# Isolated-ARD.net
KiCad netlist of a schematic drawn in EAGLE
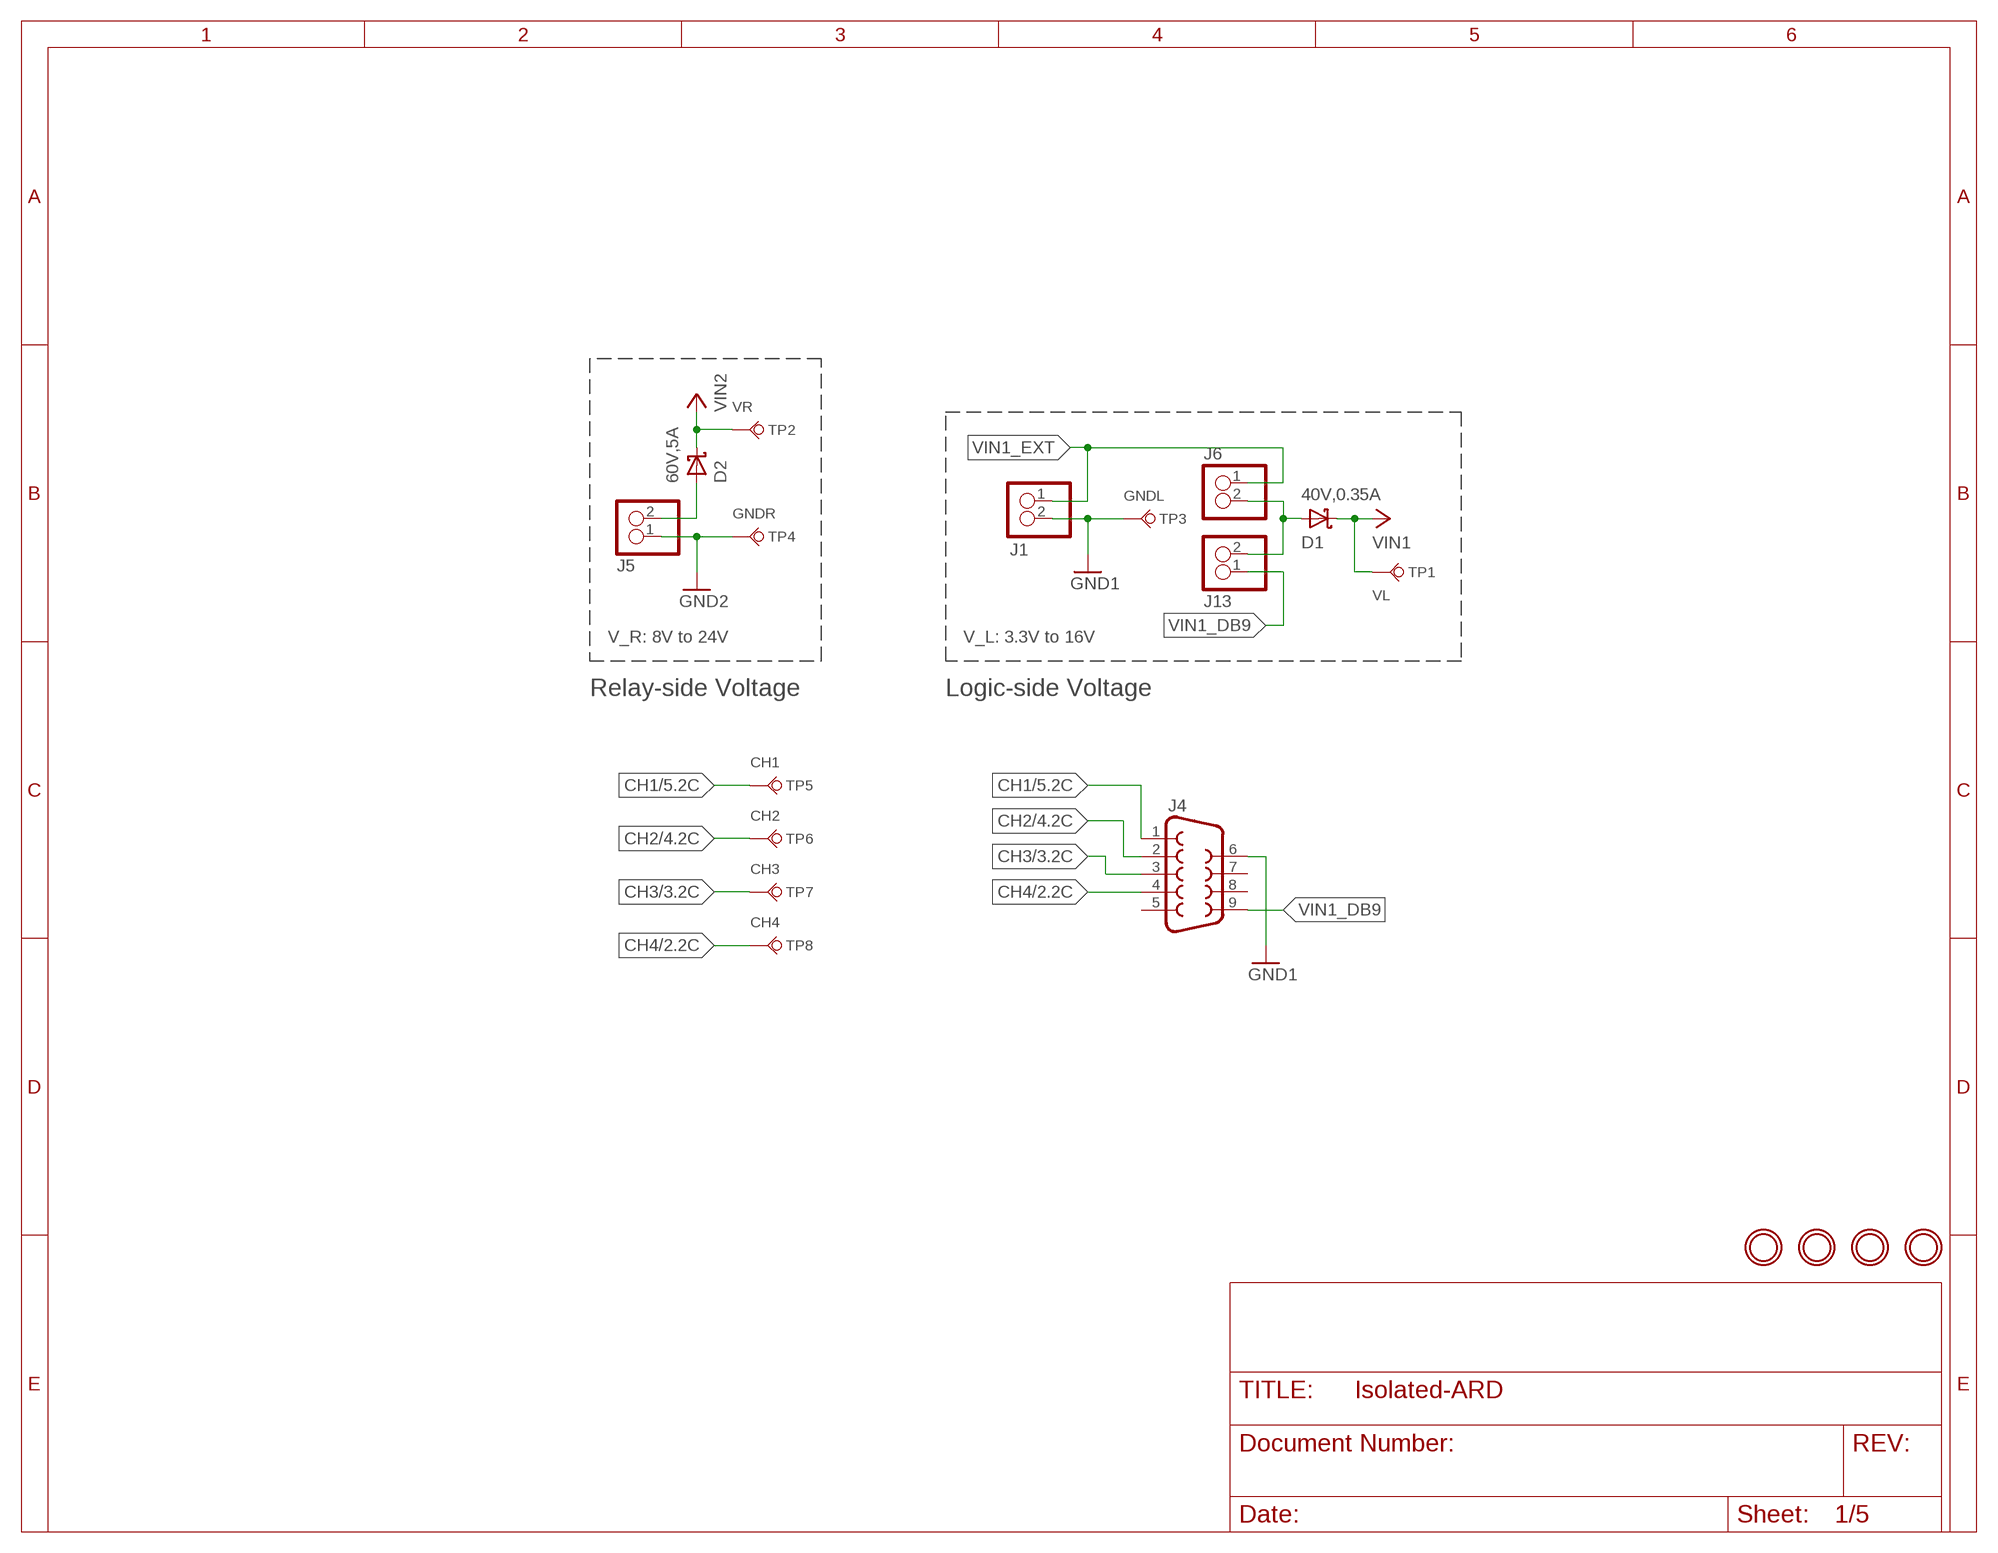
[diagram p0: schematic, sheet 1]
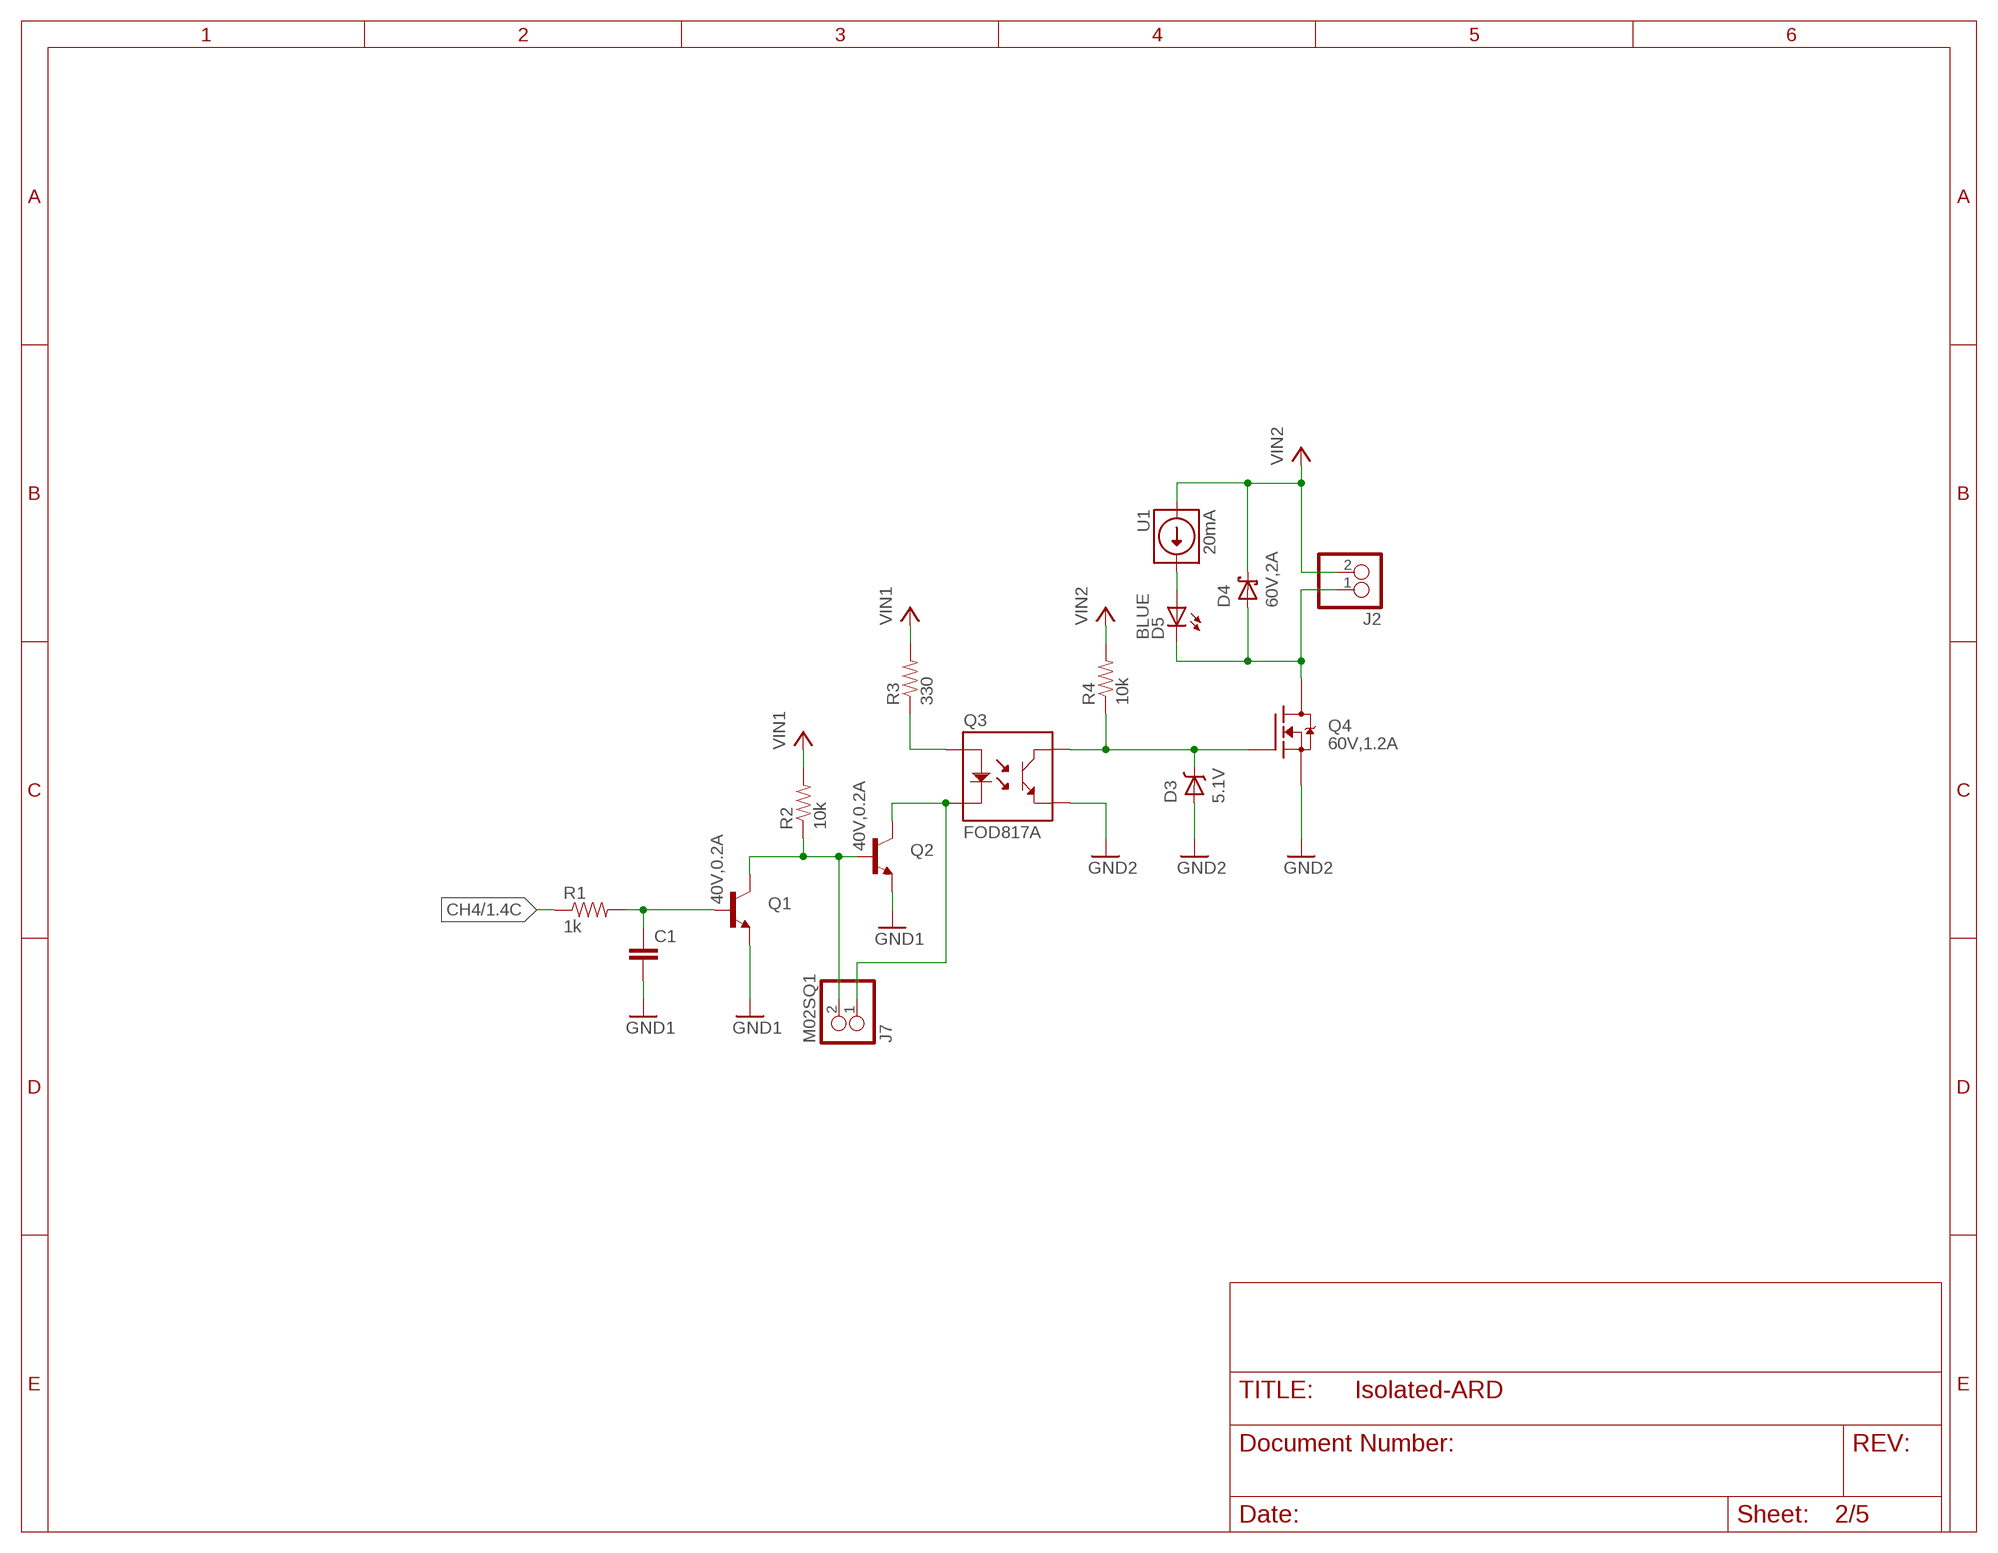
[diagram p1: schematic, sheet 2]
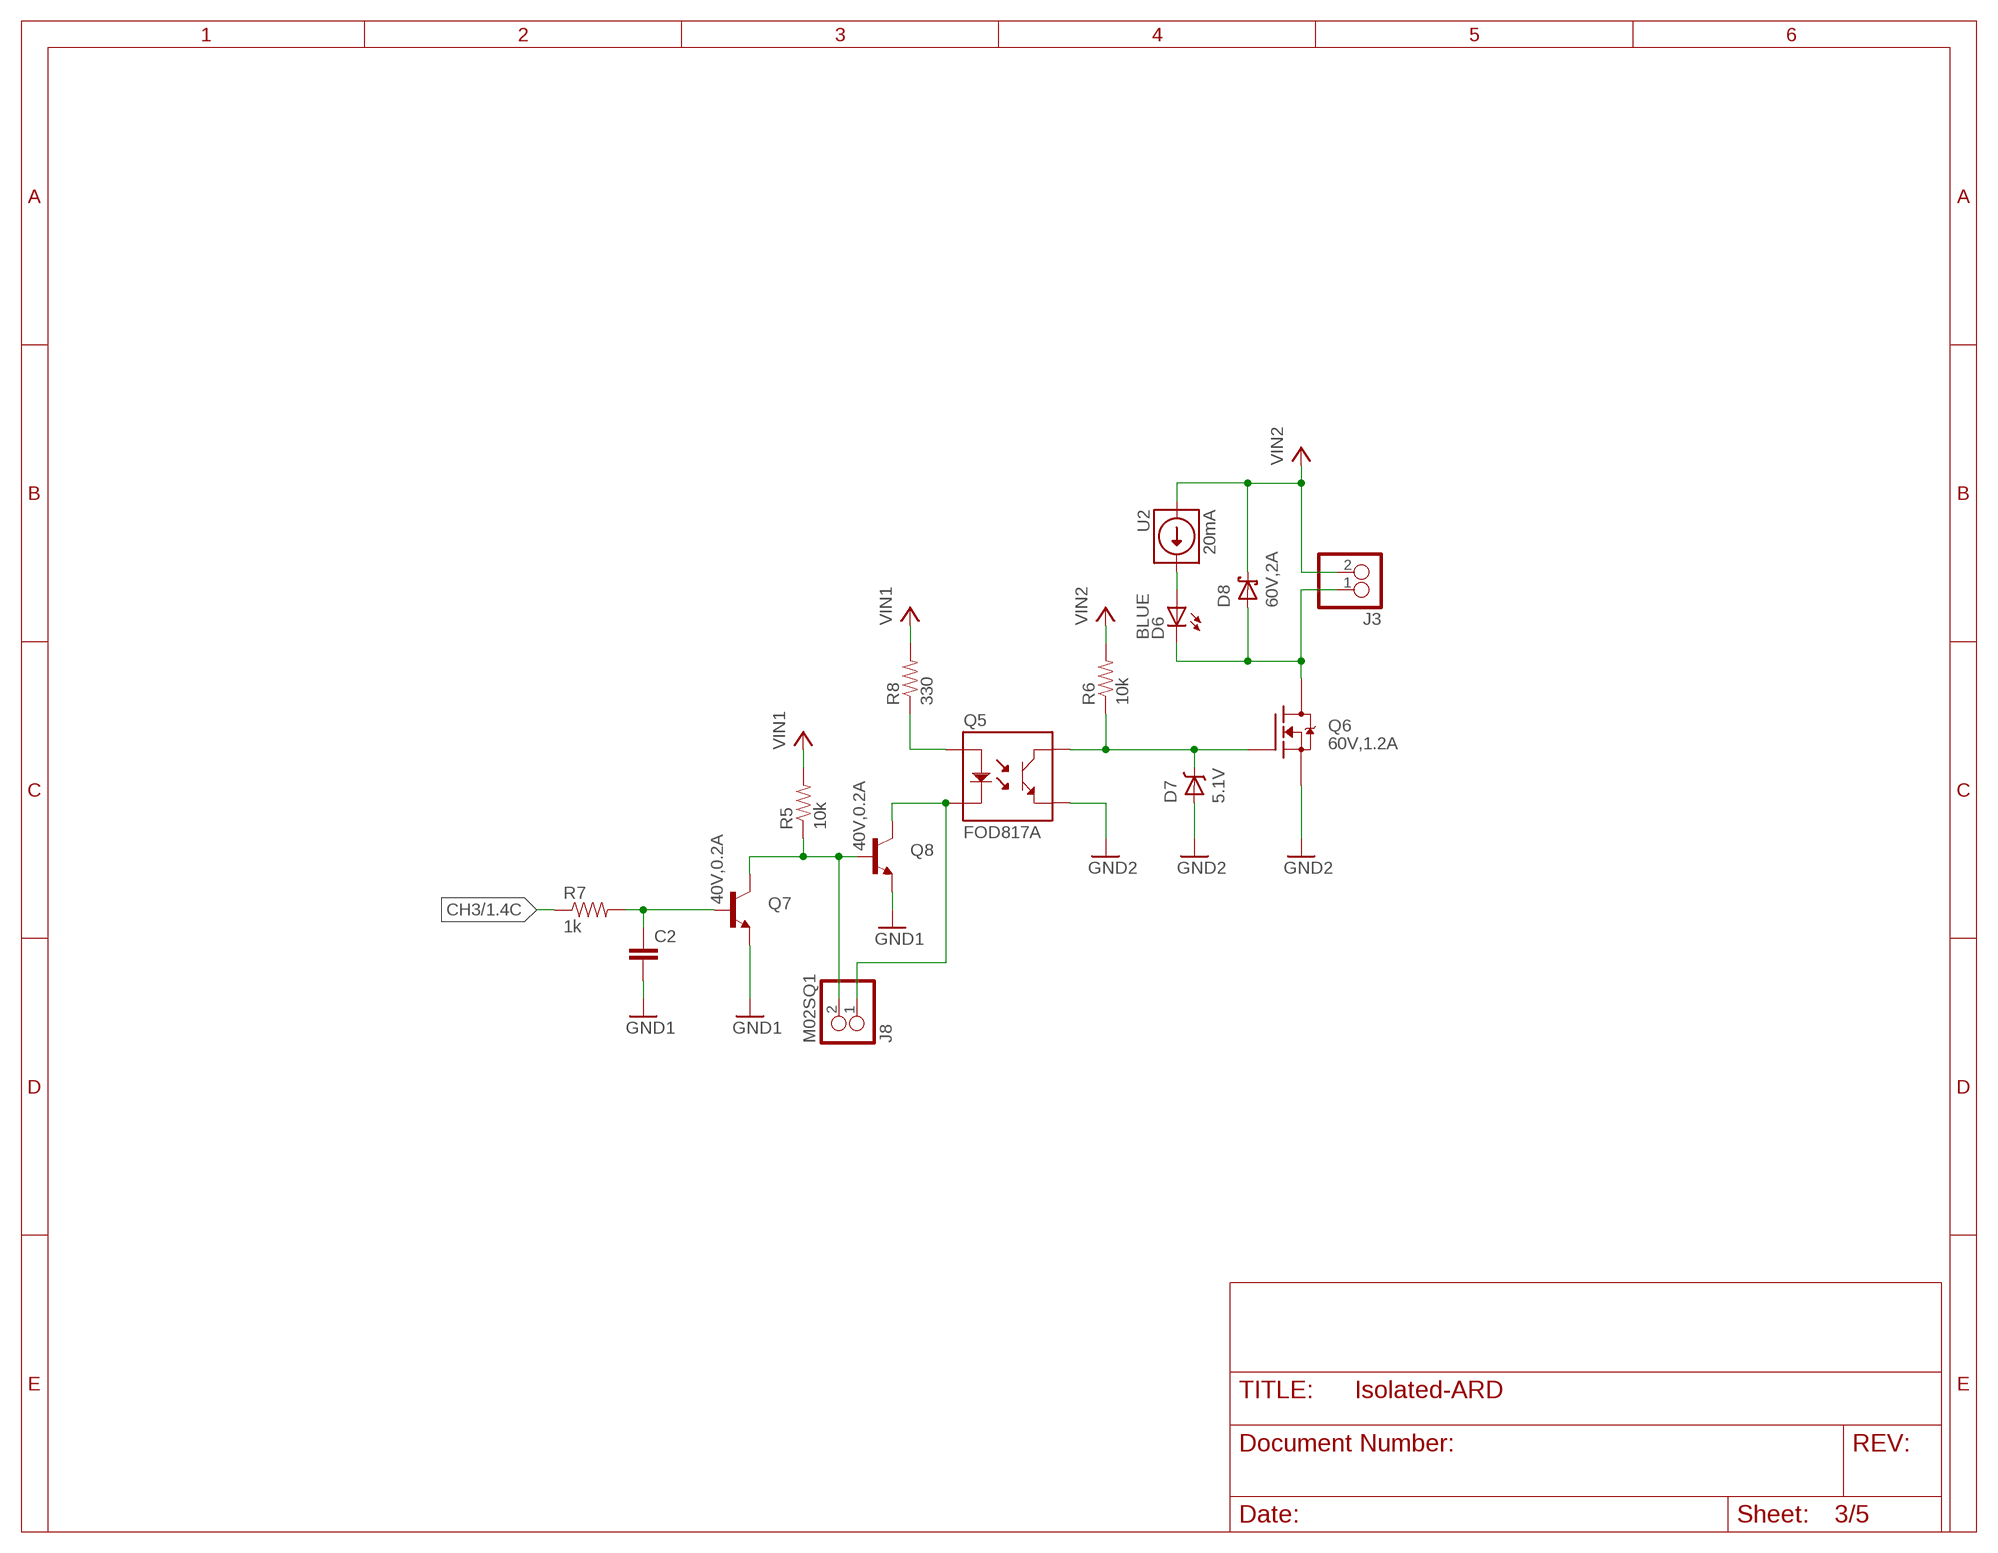
[diagram p2: schematic, sheet 3]
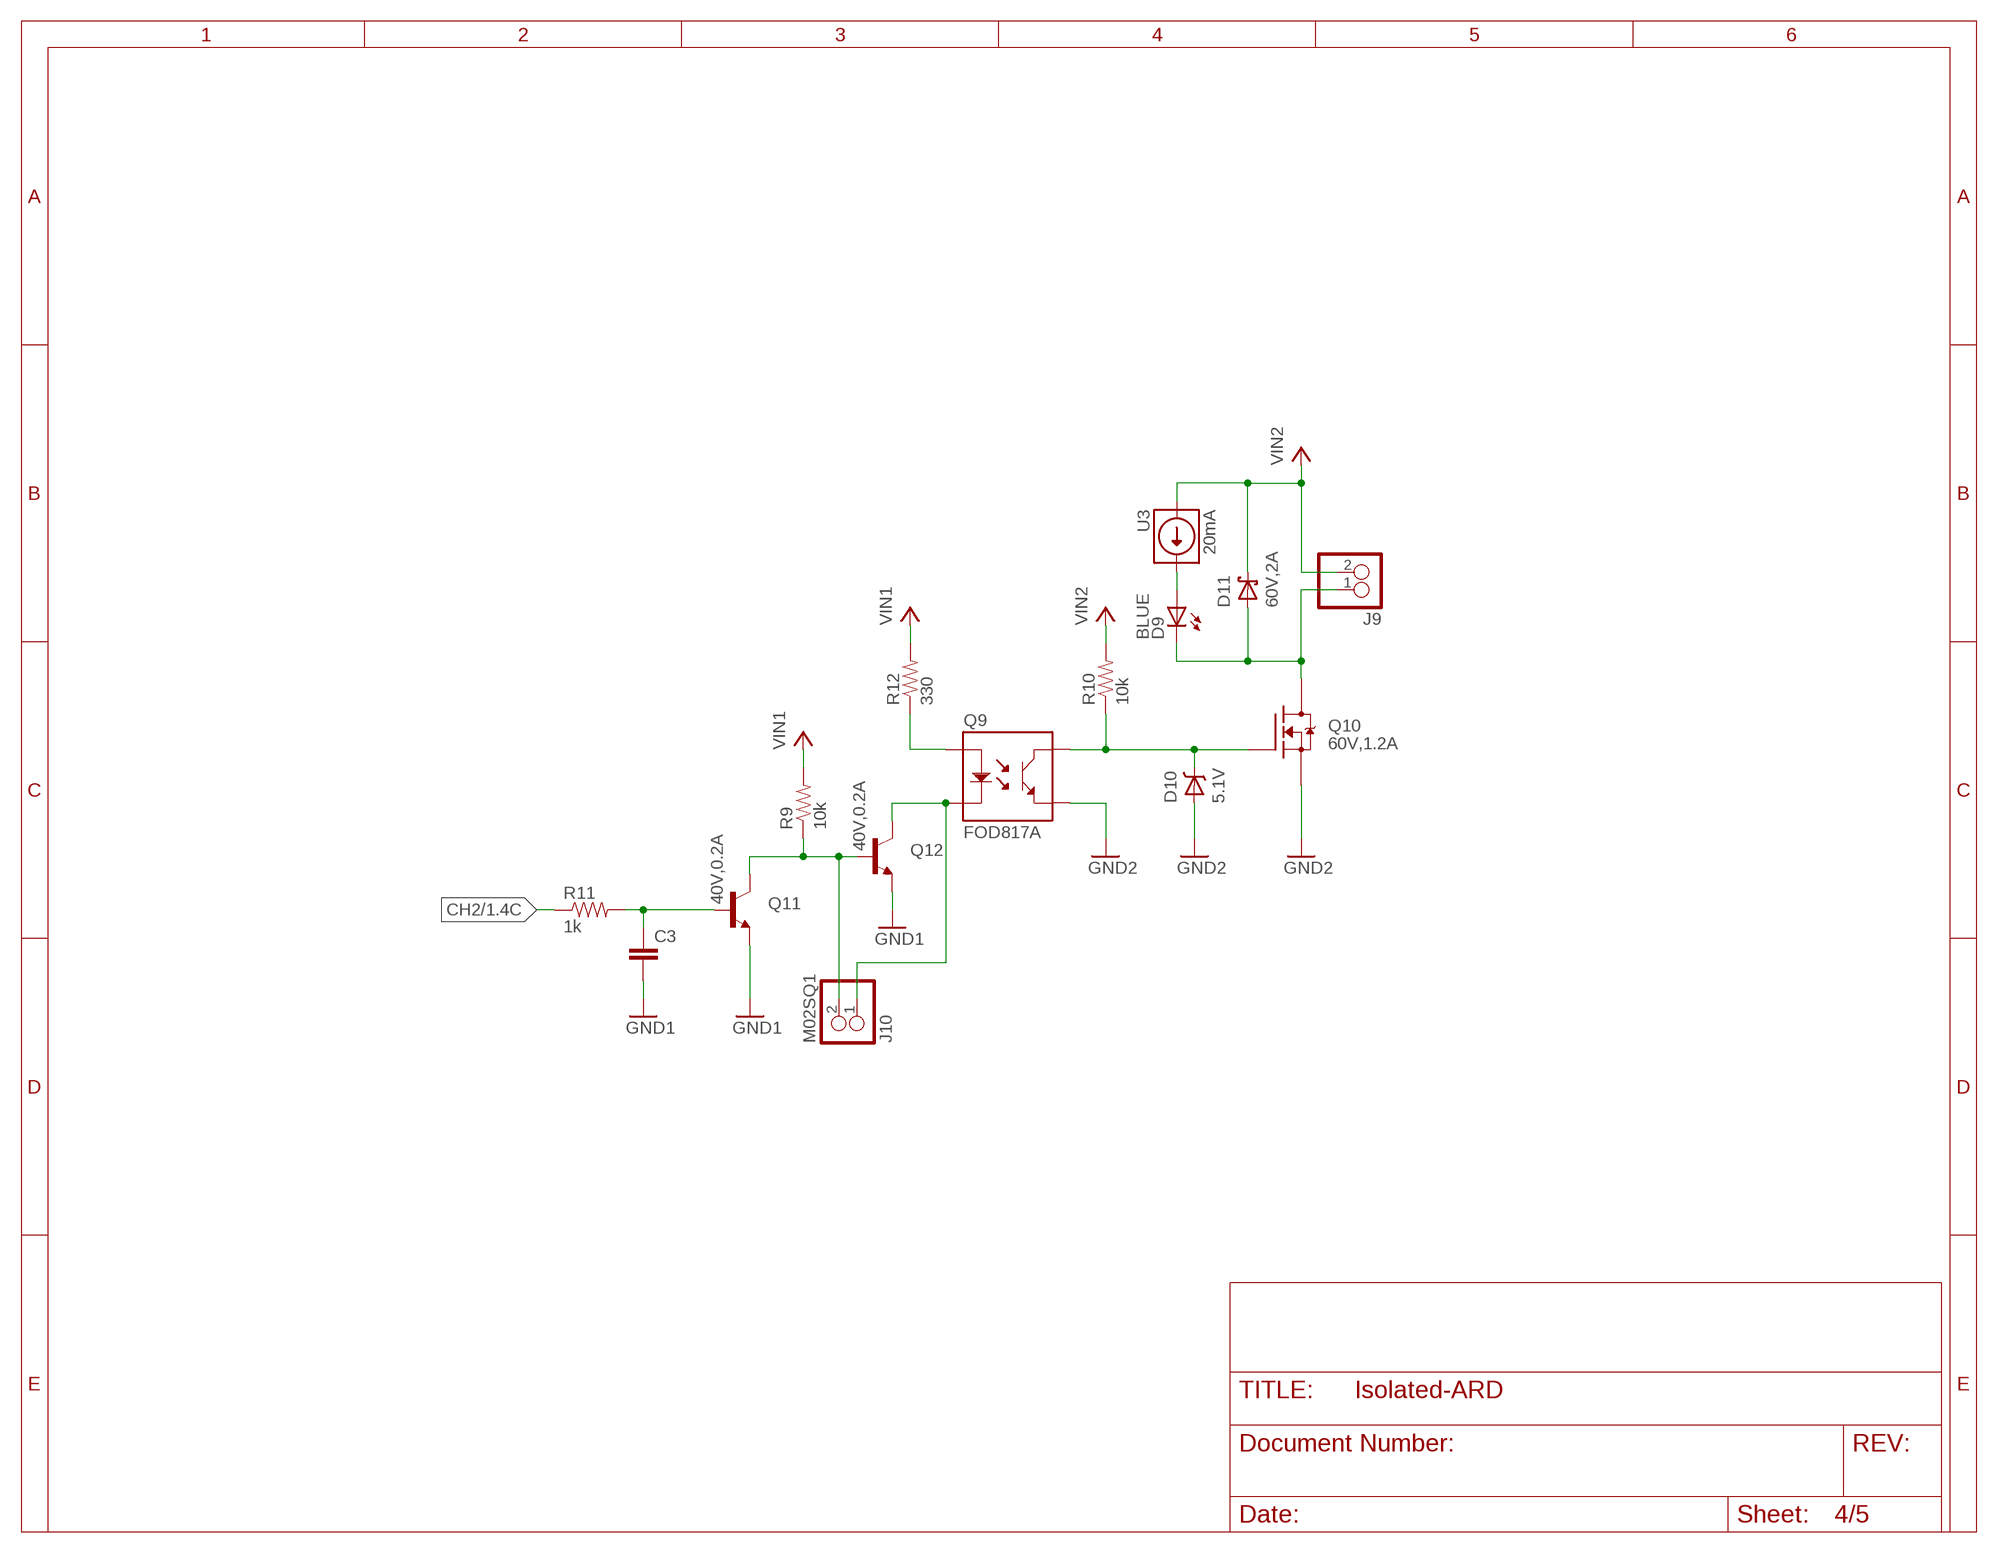
[diagram p3: schematic, sheet 4]
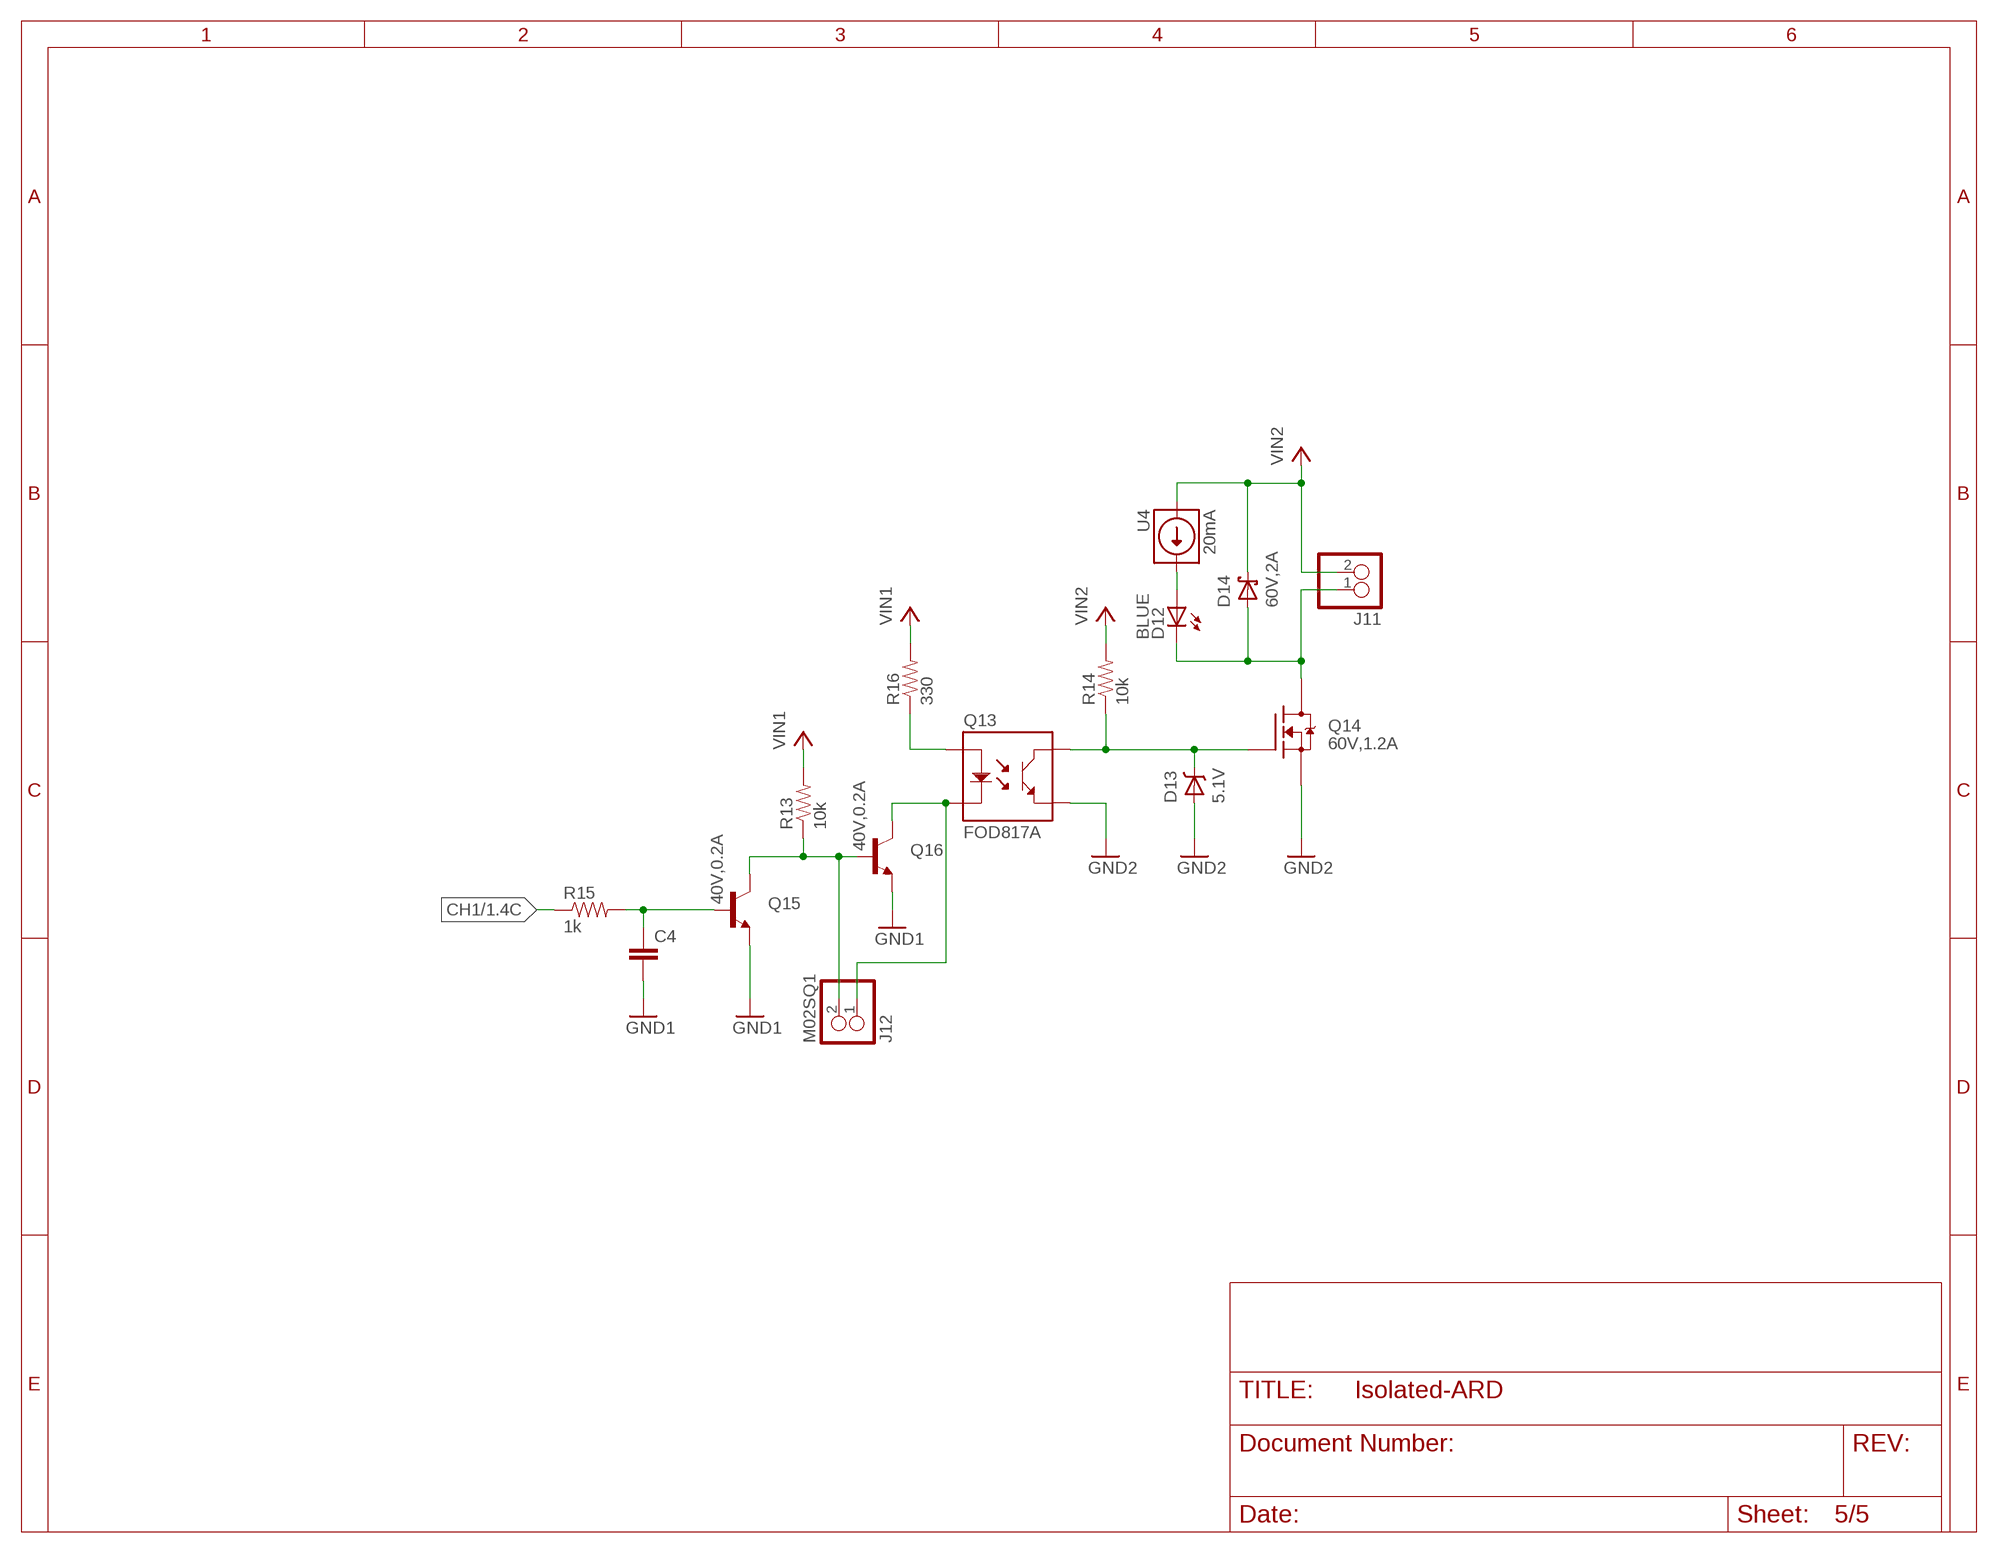
[diagram p4: schematic, sheet 5]

(export (version "E")
  (design (tool "Eeschema 10.0.6"))
  (components
    (comp (ref "C3")
      (value "C-0805")
      (footprint "eagle-import:0805-CAP")
      (libsource (lib "eagle-import") (part "C-0805"))
    )
    (comp (ref "D9")
      (value "BLUE")
      (footprint "eagle-import:1206-LED")
      (fields
        (field (name "MFR") "Lite-On Inc.")
        (field (name "MPN") "LTST-C150KBKT")
        (field (name "DESC") "Clear Blue LED, 1206, 3.3V Vf, 20mA")
        (field (name "DIGIKEY_OC") "160-1643-1-ND")
        (field (name "MPN_1") "LTST-C150KBKT")
      )
      (libsource (lib "eagle-import") (part "LTST-C?KKT150B"))
    )
    (comp (ref "D10")
      (value "5.1V")
      (footprint "eagle-import:SOD-123")
      (fields (field (name "MFR") "Diodes Incorporated") (field (name "MPN") "MMSZ5231B-7-F"))
      (libsource (lib "eagle-import") (part "MMSZ52B?-7-F31"))
    )
    (comp (ref "D11")
      (value "60V,2A")
      (footprint "eagle-import:SMA-DIODE")
      (fields (field (name "MFR") "Diodes Incorporated") (field (name "MPN") "B260A-13-F"))
      (libsource (lib "eagle-import") (part "B2A-13-F60"))
    )
    (comp (ref "J9")
      (value "M02SKT-3.5MM-R90")
      (footprint "eagle-import:SOCKET-3.5MM-2-R90")
      (libsource (lib "eagle-import") (part "M02?SKT-3.5MM-R90"))
    )
    (comp (ref "J10")
      (value "M02SQ1")
      (footprint "eagle-import:1X02_SQ1")
      (libsource (lib "eagle-import") (part "M02?SQ1"))
    )
    (comp (ref "Q9")
      (value "FOD817A")
      (footprint "eagle-import:4-SMD")
      (fields (field (name "MFR") "Fairchild Semiconductor") (field (name "MPN") "FOD817DSD"))
      (libsource (lib "eagle-import") (part "FOD817A"))
    )
    (comp (ref "Q10")
      (value "60V,1.2A")
      (footprint "eagle-import:SOT23-3")
      (fields (field (name "MFR") "International Rectifier") (field (name "MPN") "IRLML2060TRPBF"))
      (libsource (lib "eagle-import") (part "IRLML2060TRPBF"))
    )
    (comp (ref "Q11")
      (value "40V,0.2A")
      (footprint "eagle-import:SOT23-3")
      (fields (field (name "MFR") "Diodes Incorporated") (field (name "MPN") "MMBT3904-7-F"))
      (libsource (lib "eagle-import") (part "MMBT3904"))
    )
    (comp (ref "Q12")
      (value "40V,0.2A")
      (footprint "eagle-import:SOT23-3")
      (fields (field (name "MFR") "Diodes Incorporated") (field (name "MPN") "MMBT3904-7-F"))
      (libsource (lib "eagle-import") (part "MMBT3904"))
    )
    (comp (ref "R9")
      (value "10k")
      (footprint "eagle-import:0805-RES")
      (fields
        (field (name "MFR") "Panasonic Electronic Components")
        (field (name "MPN") "ERJ-6GEYJ103V")
        (field (name "POWER") "0.125W")
      )
      (libsource (lib "eagle-import") (part "10K--?08055%"))
    )
    (comp (ref "R10")
      (value "10k")
      (footprint "eagle-import:0805-RES")
      (fields
        (field (name "MFR") "Panasonic Electronic Components")
        (field (name "MPN") "ERJ-6GEYJ103V")
        (field (name "POWER") "0.125W")
        (field (name "DESC") "RES 10K OHM 1/8W 5% 0805 SMD")
        (field (name "DIGIKEY_OC") "P10KACT-ND")
        (field (name "MFR_1") "Panasonic Electronic Components")
        (field (name "MPN_1") "ERJ-6GEYJ103V")
        (field (name "POWER_1") "0.125W")
      )
      (libsource (lib "eagle-import") (part "10K--?08055%"))
    )
    (comp (ref "R11")
      (value "1k")
      (footprint "eagle-import:0805-RES")
      (fields
        (field (name "MFR") "Panasonic Electronic Components")
        (field (name "MPN") "ERJ-6GEYJ102V")
        (field (name "POWER") "0.125W")
      )
      (libsource (lib "eagle-import") (part "1K--?08055%"))
    )
    (comp (ref "R12")
      (value "330")
      (footprint "eagle-import:0805-RES")
      (fields
        (field (name "MFR") "Panasonic Electronic Components")
        (field (name "MPN") "ERJ-6GEYJ331V")
        (field (name "POWER") "0.125W")
      )
      (libsource (lib "eagle-import") (part "330--?08055%"))
    )
    (comp (ref "U3")
      (value "20mA")
      (footprint "eagle-import:SOD-123")
      (fields (field (name "MFR") "ON Semiconductor") (field (name "MPN") "NSI45020T1G"))
      (libsource (lib "eagle-import") (part "NSI45020T1G"))
    )
    (comp (ref "D1")
      (value "40V,0.35A")
      (footprint "eagle-import:SOD-323")
      (fields (field (name "MFR") "Diodes Incorporated") (field (name "MPN") "SD103AWS-7-F"))
      (libsource (lib "eagle-import") (part "SD103-7-FAWS"))
    )
    (comp (ref "D2")
      (value "60V,5A")
      (footprint "eagle-import:SMC-DIODE")
      (fields (field (name "MFR") "Diodes Incorporated") (field (name "MPN") "B560C-13-F"))
      (libsource (lib "eagle-import") (part "B5C-13-F60"))
    )
    (comp (ref "J1")
      (value "M02SKT-3.5MM-R90")
      (footprint "eagle-import:SOCKET-3.5MM-2-R90")
      (libsource (lib "eagle-import") (part "M02?SKT-3.5MM-R90"))
    )
    (comp (ref "J4")
      (value "DB9-R90-F")
      (footprint "eagle-import:DB9-R90")
      (fields (field (name "MFR") "TE Connectivity") (field (name "MPN") "1734354-1"))
      (libsource (lib "eagle-import") (part "DB9-R90-F"))
    )
    (comp (ref "J5")
      (value "M02SKT-3.5MM-R90")
      (footprint "eagle-import:SOCKET-3.5MM-2-R90")
      (libsource (lib "eagle-import") (part "M02?SKT-3.5MM-R90"))
    )
    (comp (ref "J6")
      (value "M02SQ1")
      (footprint "eagle-import:1X02_SQ1")
      (libsource (lib "eagle-import") (part "M02?SQ1"))
    )
    (comp (ref "J13")
      (value "M02SQ1")
      (footprint "eagle-import:1X02_SQ1")
      (libsource (lib "eagle-import") (part "M02?SQ1"))
    )
    (comp (ref "TP1")
      (value "TP-THRU-R")
      (footprint "eagle-import:TP_THRU_CIRC")
      (fields (field (name "TP_SIG_NAME") "VL"))
      (libsource (lib "eagle-import") (part "TP-?THRU-R"))
    )
    (comp (ref "TP2")
      (value "TP-THRU-R")
      (footprint "eagle-import:TP_THRU_CIRC")
      (fields (field (name "TP_SIG_NAME") "VR"))
      (libsource (lib "eagle-import") (part "TP-?THRU-R"))
    )
    (comp (ref "TP3")
      (value "TP-THRU-B")
      (footprint "eagle-import:TP_THRU_CIRC")
      (fields (field (name "TP_SIG_NAME") "GNDL"))
      (libsource (lib "eagle-import") (part "TP-?THRU-B"))
    )
    (comp (ref "TP4")
      (value "TP-THRU-B")
      (footprint "eagle-import:TP_THRU_CIRC")
      (fields (field (name "TP_SIG_NAME") "GNDR"))
      (libsource (lib "eagle-import") (part "TP-?THRU-B"))
    )
    (comp (ref "TP5")
      (value "TP-THRU-B")
      (footprint "eagle-import:TP_THRU_CIRC")
      (fields (field (name "TP_COLOR") "B") (field (name "TP_SIG_NAME") "CH1"))
      (libsource (lib "eagle-import") (part "TP-?THRU-B"))
    )
    (comp (ref "TP6")
      (value "TP-THRU-B")
      (footprint "eagle-import:TP_THRU_CIRC")
      (fields (field (name "TP_COLOR") "B") (field (name "TP_SIG_NAME") "CH2"))
      (libsource (lib "eagle-import") (part "TP-?THRU-B"))
    )
    (comp (ref "TP7")
      (value "TP-THRU-B")
      (footprint "eagle-import:TP_THRU_CIRC")
      (fields (field (name "TP_COLOR") "B") (field (name "TP_SIG_NAME") "CH3"))
      (libsource (lib "eagle-import") (part "TP-?THRU-B"))
    )
    (comp (ref "TP8")
      (value "TP-THRU-B")
      (footprint "eagle-import:TP_THRU_CIRC")
      (fields (field (name "TP_COLOR") "B") (field (name "TP_SIG_NAME") "CH4"))
      (libsource (lib "eagle-import") (part "TP-?THRU-B"))
    )
    (comp (ref "U$13")
      (value "MNTHOLE-M3")
      (footprint "eagle-import:MNTHOLE_M3_PLATED")
      (libsource (lib "eagle-import") (part "MNTHOLE-?M3"))
    )
    (comp (ref "U$14")
      (value "MNTHOLE-M3")
      (footprint "eagle-import:MNTHOLE_M3_PLATED")
      (libsource (lib "eagle-import") (part "MNTHOLE-?M3"))
    )
    (comp (ref "U$15")
      (value "MNTHOLE-M3")
      (footprint "eagle-import:MNTHOLE_M3_PLATED")
      (libsource (lib "eagle-import") (part "MNTHOLE-?M3"))
    )
    (comp (ref "U$21")
      (value "MNTHOLE-M3")
      (footprint "eagle-import:MNTHOLE_M3_PLATED")
      (libsource (lib "eagle-import") (part "MNTHOLE-?M3"))
    )
    (comp (ref "C2")
      (value "C-0805")
      (footprint "eagle-import:0805-CAP")
      (libsource (lib "eagle-import") (part "C-0805"))
    )
    (comp (ref "D6")
      (value "BLUE")
      (footprint "eagle-import:1206-LED")
      (fields
        (field (name "MFR") "Lite-On Inc.")
        (field (name "MPN") "LTST-C150KBKT")
        (field (name "DESC") "Clear Blue LED, 1206, 3.3V Vf, 20mA")
        (field (name "DIGIKEY_OC") "160-1643-1-ND")
        (field (name "MPN_1") "LTST-C150KBKT")
      )
      (libsource (lib "eagle-import") (part "LTST-C?KKT150B"))
    )
    (comp (ref "D7")
      (value "5.1V")
      (footprint "eagle-import:SOD-123")
      (fields (field (name "MFR") "Diodes Incorporated") (field (name "MPN") "MMSZ5231B-7-F"))
      (libsource (lib "eagle-import") (part "MMSZ52B?-7-F31"))
    )
    (comp (ref "D8")
      (value "60V,2A")
      (footprint "eagle-import:SMA-DIODE")
      (fields (field (name "MFR") "Diodes Incorporated") (field (name "MPN") "B260A-13-F"))
      (libsource (lib "eagle-import") (part "B2A-13-F60"))
    )
    (comp (ref "J3")
      (value "M02SKT-3.5MM-R90")
      (footprint "eagle-import:SOCKET-3.5MM-2-R90")
      (libsource (lib "eagle-import") (part "M02?SKT-3.5MM-R90"))
    )
    (comp (ref "J8")
      (value "M02SQ1")
      (footprint "eagle-import:1X02_SQ1")
      (libsource (lib "eagle-import") (part "M02?SQ1"))
    )
    (comp (ref "Q5")
      (value "FOD817A")
      (footprint "eagle-import:4-SMD")
      (fields (field (name "MFR") "Fairchild Semiconductor") (field (name "MPN") "FOD817DSD"))
      (libsource (lib "eagle-import") (part "FOD817A"))
    )
    (comp (ref "Q6")
      (value "60V,1.2A")
      (footprint "eagle-import:SOT23-3")
      (fields (field (name "MFR") "International Rectifier") (field (name "MPN") "IRLML2060TRPBF"))
      (libsource (lib "eagle-import") (part "IRLML2060TRPBF"))
    )
    (comp (ref "Q7")
      (value "40V,0.2A")
      (footprint "eagle-import:SOT23-3")
      (fields (field (name "MFR") "Diodes Incorporated") (field (name "MPN") "MMBT3904-7-F"))
      (libsource (lib "eagle-import") (part "MMBT3904"))
    )
    (comp (ref "Q8")
      (value "40V,0.2A")
      (footprint "eagle-import:SOT23-3")
      (fields (field (name "MFR") "Diodes Incorporated") (field (name "MPN") "MMBT3904-7-F"))
      (libsource (lib "eagle-import") (part "MMBT3904"))
    )
    (comp (ref "R5")
      (value "10k")
      (footprint "eagle-import:0805-RES")
      (fields
        (field (name "MFR") "Panasonic Electronic Components")
        (field (name "MPN") "ERJ-6GEYJ103V")
        (field (name "POWER") "0.125W")
      )
      (libsource (lib "eagle-import") (part "10K--?08055%"))
    )
    (comp (ref "R6")
      (value "10k")
      (footprint "eagle-import:0805-RES")
      (fields
        (field (name "MFR") "Panasonic Electronic Components")
        (field (name "MPN") "ERJ-6GEYJ103V")
        (field (name "POWER") "0.125W")
        (field (name "DESC") "RES 10K OHM 1/8W 5% 0805 SMD")
        (field (name "DIGIKEY_OC") "P10KACT-ND")
        (field (name "MFR_1") "Panasonic Electronic Components")
        (field (name "MPN_1") "ERJ-6GEYJ103V")
        (field (name "POWER_1") "0.125W")
      )
      (libsource (lib "eagle-import") (part "10K--?08055%"))
    )
    (comp (ref "R7")
      (value "1k")
      (footprint "eagle-import:0805-RES")
      (fields
        (field (name "MFR") "Panasonic Electronic Components")
        (field (name "MPN") "ERJ-6GEYJ102V")
        (field (name "POWER") "0.125W")
      )
      (libsource (lib "eagle-import") (part "1K--?08055%"))
    )
    (comp (ref "R8")
      (value "330")
      (footprint "eagle-import:0805-RES")
      (fields
        (field (name "MFR") "Panasonic Electronic Components")
        (field (name "MPN") "ERJ-6GEYJ331V")
        (field (name "POWER") "0.125W")
      )
      (libsource (lib "eagle-import") (part "330--?08055%"))
    )
    (comp (ref "U2")
      (value "20mA")
      (footprint "eagle-import:SOD-123")
      (fields (field (name "MFR") "ON Semiconductor") (field (name "MPN") "NSI45020T1G"))
      (libsource (lib "eagle-import") (part "NSI45020T1G"))
    )
    (comp (ref "C1")
      (value "C-0805")
      (footprint "eagle-import:0805-CAP")
      (libsource (lib "eagle-import") (part "C-0805"))
    )
    (comp (ref "D3")
      (value "5.1V")
      (footprint "eagle-import:SOD-123")
      (fields (field (name "MFR") "Diodes Incorporated") (field (name "MPN") "MMSZ5231B-7-F"))
      (libsource (lib "eagle-import") (part "MMSZ52B?-7-F31"))
    )
    (comp (ref "D4")
      (value "60V,2A")
      (footprint "eagle-import:SMA-DIODE")
      (fields (field (name "MFR") "Diodes Incorporated") (field (name "MPN") "B260A-13-F"))
      (libsource (lib "eagle-import") (part "B2A-13-F60"))
    )
    (comp (ref "D5")
      (value "BLUE")
      (footprint "eagle-import:1206-LED")
      (fields
        (field (name "MFR") "Lite-On Inc.")
        (field (name "MPN") "LTST-C150KBKT")
        (field (name "DESC") "Clear Blue LED, 1206, 3.3V Vf, 20mA")
        (field (name "DIGIKEY_OC") "160-1643-1-ND")
        (field (name "MPN_1") "LTST-C150KBKT")
      )
      (libsource (lib "eagle-import") (part "LTST-C?KKT150B"))
    )
    (comp (ref "J2")
      (value "M02SKT-3.5MM-R90")
      (footprint "eagle-import:SOCKET-3.5MM-2-R90")
      (libsource (lib "eagle-import") (part "M02?SKT-3.5MM-R90"))
    )
    (comp (ref "J7")
      (value "M02SQ1")
      (footprint "eagle-import:1X02_SQ1")
      (libsource (lib "eagle-import") (part "M02?SQ1"))
    )
    (comp (ref "Q1")
      (value "40V,0.2A")
      (footprint "eagle-import:SOT23-3")
      (fields (field (name "MFR") "Diodes Incorporated") (field (name "MPN") "MMBT3904-7-F"))
      (libsource (lib "eagle-import") (part "MMBT3904"))
    )
    (comp (ref "Q2")
      (value "40V,0.2A")
      (footprint "eagle-import:SOT23-3")
      (fields (field (name "MFR") "Diodes Incorporated") (field (name "MPN") "MMBT3904-7-F"))
      (libsource (lib "eagle-import") (part "MMBT3904"))
    )
    (comp (ref "Q3")
      (value "FOD817A")
      (footprint "eagle-import:4-SMD")
      (fields (field (name "MFR") "Fairchild Semiconductor") (field (name "MPN") "FOD817DSD"))
      (libsource (lib "eagle-import") (part "FOD817A"))
    )
    (comp (ref "Q4")
      (value "60V,1.2A")
      (footprint "eagle-import:SOT23-3")
      (fields (field (name "MFR") "International Rectifier") (field (name "MPN") "IRLML2060TRPBF"))
      (libsource (lib "eagle-import") (part "IRLML2060TRPBF"))
    )
    (comp (ref "R1")
      (value "1k")
      (footprint "eagle-import:0805-RES")
      (fields
        (field (name "MFR") "Panasonic Electronic Components")
        (field (name "MPN") "ERJ-6GEYJ102V")
        (field (name "POWER") "0.125W")
      )
      (libsource (lib "eagle-import") (part "1K--?08055%"))
    )
    (comp (ref "R2")
      (value "10k")
      (footprint "eagle-import:0805-RES")
      (fields
        (field (name "MFR") "Panasonic Electronic Components")
        (field (name "MPN") "ERJ-6GEYJ103V")
        (field (name "POWER") "0.125W")
      )
      (libsource (lib "eagle-import") (part "10K--?08055%"))
    )
    (comp (ref "R3")
      (value "330")
      (footprint "eagle-import:0805-RES")
      (fields
        (field (name "MFR") "Panasonic Electronic Components")
        (field (name "MPN") "ERJ-6GEYJ331V")
        (field (name "POWER") "0.125W")
      )
      (libsource (lib "eagle-import") (part "330--?08055%"))
    )
    (comp (ref "R4")
      (value "10k")
      (footprint "eagle-import:0805-RES")
      (fields
        (field (name "MFR") "Panasonic Electronic Components")
        (field (name "MPN") "ERJ-6GEYJ103V")
        (field (name "POWER") "0.125W")
        (field (name "DESC") "RES 10K OHM 1/8W 5% 0805 SMD")
        (field (name "DIGIKEY_OC") "P10KACT-ND")
        (field (name "MFR_1") "Panasonic Electronic Components")
        (field (name "MPN_1") "ERJ-6GEYJ103V")
        (field (name "POWER_1") "0.125W")
      )
      (libsource (lib "eagle-import") (part "10K--?08055%"))
    )
    (comp (ref "U1")
      (value "20mA")
      (footprint "eagle-import:SOD-123")
      (fields (field (name "MFR") "ON Semiconductor") (field (name "MPN") "NSI45020T1G"))
      (libsource (lib "eagle-import") (part "NSI45020T1G"))
    )
    (comp (ref "C4")
      (value "C-0805")
      (footprint "eagle-import:0805-CAP")
      (libsource (lib "eagle-import") (part "C-0805"))
    )
    (comp (ref "D12")
      (value "BLUE")
      (footprint "eagle-import:1206-LED")
      (fields
        (field (name "MFR") "Lite-On Inc.")
        (field (name "MPN") "LTST-C150KBKT")
        (field (name "DESC") "Clear Blue LED, 1206, 3.3V Vf, 20mA")
        (field (name "DIGIKEY_OC") "160-1643-1-ND")
        (field (name "MPN_1") "LTST-C150KBKT")
      )
      (libsource (lib "eagle-import") (part "LTST-C?KKT150B"))
    )
    (comp (ref "D13")
      (value "5.1V")
      (footprint "eagle-import:SOD-123")
      (fields (field (name "MFR") "Diodes Incorporated") (field (name "MPN") "MMSZ5231B-7-F"))
      (libsource (lib "eagle-import") (part "MMSZ52B?-7-F31"))
    )
    (comp (ref "D14")
      (value "60V,2A")
      (footprint "eagle-import:SMA-DIODE")
      (fields (field (name "MFR") "Diodes Incorporated") (field (name "MPN") "B260A-13-F"))
      (libsource (lib "eagle-import") (part "B2A-13-F60"))
    )
    (comp (ref "J11")
      (value "M02SKT-3.5MM-R90")
      (footprint "eagle-import:SOCKET-3.5MM-2-R90")
      (libsource (lib "eagle-import") (part "M02?SKT-3.5MM-R90"))
    )
    (comp (ref "J12")
      (value "M02SQ1")
      (footprint "eagle-import:1X02_SQ1")
      (libsource (lib "eagle-import") (part "M02?SQ1"))
    )
    (comp (ref "Q13")
      (value "FOD817A")
      (footprint "eagle-import:4-SMD")
      (fields (field (name "MFR") "Fairchild Semiconductor") (field (name "MPN") "FOD817DSD"))
      (libsource (lib "eagle-import") (part "FOD817A"))
    )
    (comp (ref "Q14")
      (value "60V,1.2A")
      (footprint "eagle-import:SOT23-3")
      (fields (field (name "MFR") "International Rectifier") (field (name "MPN") "IRLML2060TRPBF"))
      (libsource (lib "eagle-import") (part "IRLML2060TRPBF"))
    )
    (comp (ref "Q15")
      (value "40V,0.2A")
      (footprint "eagle-import:SOT23-3")
      (fields (field (name "MFR") "Diodes Incorporated") (field (name "MPN") "MMBT3904-7-F"))
      (libsource (lib "eagle-import") (part "MMBT3904"))
    )
    (comp (ref "Q16")
      (value "40V,0.2A")
      (footprint "eagle-import:SOT23-3")
      (fields (field (name "MFR") "Diodes Incorporated") (field (name "MPN") "MMBT3904-7-F"))
      (libsource (lib "eagle-import") (part "MMBT3904"))
    )
    (comp (ref "R13")
      (value "10k")
      (footprint "eagle-import:0805-RES")
      (fields
        (field (name "MFR") "Panasonic Electronic Components")
        (field (name "MPN") "ERJ-6GEYJ103V")
        (field (name "POWER") "0.125W")
      )
      (libsource (lib "eagle-import") (part "10K--?08055%"))
    )
    (comp (ref "R14")
      (value "10k")
      (footprint "eagle-import:0805-RES")
      (fields
        (field (name "MFR") "Panasonic Electronic Components")
        (field (name "MPN") "ERJ-6GEYJ103V")
        (field (name "POWER") "0.125W")
        (field (name "DESC") "RES 10K OHM 1/8W 5% 0805 SMD")
        (field (name "DIGIKEY_OC") "P10KACT-ND")
        (field (name "MFR_1") "Panasonic Electronic Components")
        (field (name "MPN_1") "ERJ-6GEYJ103V")
        (field (name "POWER_1") "0.125W")
      )
      (libsource (lib "eagle-import") (part "10K--?08055%"))
    )
    (comp (ref "R15")
      (value "1k")
      (footprint "eagle-import:0805-RES")
      (fields
        (field (name "MFR") "Panasonic Electronic Components")
        (field (name "MPN") "ERJ-6GEYJ102V")
        (field (name "POWER") "0.125W")
      )
      (libsource (lib "eagle-import") (part "1K--?08055%"))
    )
    (comp (ref "R16")
      (value "330")
      (footprint "eagle-import:0805-RES")
      (fields
        (field (name "MFR") "Panasonic Electronic Components")
        (field (name "MPN") "ERJ-6GEYJ331V")
        (field (name "POWER") "0.125W")
      )
      (libsource (lib "eagle-import") (part "330--?08055%"))
    )
    (comp (ref "U4")
      (value "20mA")
      (footprint "eagle-import:SOD-123")
      (fields (field (name "MFR") "ON Semiconductor") (field (name "MPN") "NSI45020T1G"))
      (libsource (lib "eagle-import") (part "NSI45020T1G"))
    )
  )
  (nets
    (net (code "1") (name "CH1") (class "Default")
      (node (ref "J4") (pin "1") (pinfunction "1_1") (pintype "passive"))
      (node (ref "R15") (pin "P$1") (pinfunction "1_P$1") (pintype "passive"))
      (node (ref "TP5") (pin "TP") (pinfunction "TP_TP") (pintype "bidirectional"))
    )
    (net (code "2") (name "CH2") (class "Default")
      (node (ref "J4") (pin "2") (pinfunction "2_2") (pintype "passive"))
      (node (ref "R11") (pin "P$1") (pinfunction "1_P$1") (pintype "passive"))
      (node (ref "TP6") (pin "TP") (pinfunction "TP_TP") (pintype "bidirectional"))
    )
    (net (code "3") (name "CH3") (class "Default")
      (node (ref "J4") (pin "3") (pinfunction "3_3") (pintype "passive"))
      (node (ref "R7") (pin "P$1") (pinfunction "1_P$1") (pintype "passive"))
      (node (ref "TP7") (pin "TP") (pinfunction "TP_TP") (pintype "bidirectional"))
    )
    (net (code "4") (name "CH4") (class "Default")
      (node (ref "J4") (pin "4") (pinfunction "4_4") (pintype "passive"))
      (node (ref "R1") (pin "P$1") (pinfunction "1_P$1") (pintype "passive"))
      (node (ref "TP8") (pin "TP") (pinfunction "TP_TP") (pintype "bidirectional"))
    )
    (net (code "5") (name "GND1") (class "Default")
      (node (ref "C1") (pin "P$2") (pinfunction "2_P$2") (pintype "passive"))
      (node (ref "C2") (pin "P$2") (pinfunction "2_P$2") (pintype "passive"))
      (node (ref "C3") (pin "P$2") (pinfunction "2_P$2") (pintype "passive"))
      (node (ref "C4") (pin "P$2") (pinfunction "2_P$2") (pintype "passive"))
      (node (ref "J1") (pin "2") (pinfunction "2_2") (pintype "bidirectional"))
      (node (ref "J4") (pin "6") (pinfunction "6_6") (pintype "passive"))
      (node (ref "Q1") (pin "2") (pinfunction "E_2") (pintype "passive"))
      (node (ref "Q11") (pin "2") (pinfunction "E_2") (pintype "passive"))
      (node (ref "Q12") (pin "2") (pinfunction "E_2") (pintype "passive"))
      (node (ref "Q15") (pin "2") (pinfunction "E_2") (pintype "passive"))
      (node (ref "Q16") (pin "2") (pinfunction "E_2") (pintype "passive"))
      (node (ref "Q2") (pin "2") (pinfunction "E_2") (pintype "passive"))
      (node (ref "Q7") (pin "2") (pinfunction "E_2") (pintype "passive"))
      (node (ref "Q8") (pin "2") (pinfunction "E_2") (pintype "passive"))
      (node (ref "TP3") (pin "TP") (pinfunction "TP_TP") (pintype "bidirectional"))
    )
    (net (code "6") (name "GND2") (class "Default")
      (node (ref "D10") (pin "A") (pinfunction "A_A") (pintype "passive"))
      (node (ref "D13") (pin "A") (pinfunction "A_A") (pintype "passive"))
      (node (ref "D3") (pin "A") (pinfunction "A_A") (pintype "passive"))
      (node (ref "D7") (pin "A") (pinfunction "A_A") (pintype "passive"))
      (node (ref "J5") (pin "1") (pinfunction "1_1") (pintype "bidirectional"))
      (node (ref "Q10") (pin "2") (pinfunction "S_2") (pintype "passive"))
      (node (ref "Q13") (pin "3") (pinfunction "T_E_3") (pintype "bidirectional"))
      (node (ref "Q14") (pin "2") (pinfunction "S_2") (pintype "passive"))
      (node (ref "Q3") (pin "3") (pinfunction "T_E_3") (pintype "bidirectional"))
      (node (ref "Q4") (pin "2") (pinfunction "S_2") (pintype "passive"))
      (node (ref "Q5") (pin "3") (pinfunction "T_E_3") (pintype "bidirectional"))
      (node (ref "Q6") (pin "2") (pinfunction "S_2") (pintype "passive"))
      (node (ref "Q9") (pin "3") (pinfunction "T_E_3") (pintype "bidirectional"))
      (node (ref "TP4") (pin "TP") (pinfunction "TP_TP") (pintype "bidirectional"))
    )
    (net (code "7") (name "Net-(C1-1)") (class "Default")
      (node (ref "C1") (pin "P$1") (pinfunction "1_P$1") (pintype "passive"))
      (node (ref "Q1") (pin "1") (pinfunction "B_1") (pintype "passive"))
      (node (ref "R1") (pin "P$2") (pinfunction "2_P$2") (pintype "passive"))
    )
    (net (code "8") (name "Net-(C2-1)") (class "Default")
      (node (ref "C2") (pin "P$1") (pinfunction "1_P$1") (pintype "passive"))
      (node (ref "Q7") (pin "1") (pinfunction "B_1") (pintype "passive"))
      (node (ref "R7") (pin "P$2") (pinfunction "2_P$2") (pintype "passive"))
    )
    (net (code "9") (name "Net-(C3-1)") (class "Default")
      (node (ref "C3") (pin "P$1") (pinfunction "1_P$1") (pintype "passive"))
      (node (ref "Q11") (pin "1") (pinfunction "B_1") (pintype "passive"))
      (node (ref "R11") (pin "P$2") (pinfunction "2_P$2") (pintype "passive"))
    )
    (net (code "10") (name "Net-(C4-1)") (class "Default")
      (node (ref "C4") (pin "P$1") (pinfunction "1_P$1") (pintype "passive"))
      (node (ref "Q15") (pin "1") (pinfunction "B_1") (pintype "passive"))
      (node (ref "R15") (pin "P$2") (pinfunction "2_P$2") (pintype "passive"))
    )
    (net (code "11") (name "Net-(D1-PadA)") (class "Default")
      (node (ref "D1") (pin "A") (pinfunction "A_A") (pintype "passive"))
      (node (ref "J13") (pin "2") (pinfunction "2_2") (pintype "bidirectional"))
      (node (ref "J6") (pin "2") (pinfunction "2_2") (pintype "bidirectional"))
    )
    (net (code "12") (name "Net-(D2-PadA)") (class "Default")
      (node (ref "D2") (pin "A") (pinfunction "A_A") (pintype "passive"))
      (node (ref "J5") (pin "2") (pinfunction "2_2") (pintype "bidirectional"))
    )
    (net (code "13") (name "Net-(D5-PadA)") (class "Default")
      (node (ref "D5") (pin "A") (pinfunction "A_A") (pintype "passive"))
      (node (ref "U1") (pin "C") (pinfunction "C_C") (pintype "bidirectional"))
    )
    (net (code "14") (name "Net-(D6-PadA)") (class "Default")
      (node (ref "D6") (pin "A") (pinfunction "A_A") (pintype "passive"))
      (node (ref "U2") (pin "C") (pinfunction "C_C") (pintype "bidirectional"))
    )
    (net (code "15") (name "Net-(D9-PadA)") (class "Default")
      (node (ref "D9") (pin "A") (pinfunction "A_A") (pintype "passive"))
      (node (ref "U3") (pin "C") (pinfunction "C_C") (pintype "bidirectional"))
    )
    (net (code "16") (name "Net-(D12-PadA)") (class "Default")
      (node (ref "D12") (pin "A") (pinfunction "A_A") (pintype "passive"))
      (node (ref "U4") (pin "C") (pinfunction "C_C") (pintype "bidirectional"))
    )
    (net (code "17") (name "Net-(Q1-C)") (class "Default")
      (node (ref "J7") (pin "2") (pinfunction "2_2") (pintype "bidirectional"))
      (node (ref "Q1") (pin "3") (pinfunction "C_3") (pintype "passive"))
      (node (ref "Q2") (pin "1") (pinfunction "B_1") (pintype "passive"))
      (node (ref "R2") (pin "P$1") (pinfunction "1_P$1") (pintype "passive"))
    )
    (net (code "18") (name "Net-(Q2-C)") (class "Default")
      (node (ref "J7") (pin "1") (pinfunction "1_1") (pintype "bidirectional"))
      (node (ref "Q2") (pin "3") (pinfunction "C_3") (pintype "passive"))
      (node (ref "Q3") (pin "2") (pinfunction "LED_C_2") (pintype "bidirectional"))
    )
    (net (code "19") (name "Net-(Q3-LED_A)") (class "Default")
      (node (ref "Q3") (pin "1") (pinfunction "LED_A_1") (pintype "bidirectional"))
      (node (ref "R3") (pin "P$1") (pinfunction "1_P$1") (pintype "passive"))
    )
    (net (code "20") (name "Net-(Q3-T_C)") (class "Default")
      (node (ref "D3") (pin "C") (pinfunction "C_C") (pintype "passive"))
      (node (ref "Q3") (pin "4") (pinfunction "T_C_4") (pintype "bidirectional"))
      (node (ref "Q4") (pin "1") (pinfunction "G_1") (pintype "passive"))
      (node (ref "R4") (pin "P$1") (pinfunction "1_P$1") (pintype "passive"))
    )
    (net (code "21") (name "Net-(Q4-D)") (class "Default")
      (node (ref "D4") (pin "A") (pinfunction "A_A") (pintype "passive"))
      (node (ref "D5") (pin "C") (pinfunction "C_C") (pintype "passive"))
      (node (ref "J2") (pin "1") (pinfunction "1_1") (pintype "bidirectional"))
      (node (ref "Q4") (pin "3") (pinfunction "D_3") (pintype "passive"))
    )
    (net (code "22") (name "Net-(Q5-LED_A)") (class "Default")
      (node (ref "Q5") (pin "1") (pinfunction "LED_A_1") (pintype "bidirectional"))
      (node (ref "R8") (pin "P$1") (pinfunction "1_P$1") (pintype "passive"))
    )
    (net (code "23") (name "Net-(Q5-LED_C)") (class "Default")
      (node (ref "J8") (pin "1") (pinfunction "1_1") (pintype "bidirectional"))
      (node (ref "Q5") (pin "2") (pinfunction "LED_C_2") (pintype "bidirectional"))
      (node (ref "Q8") (pin "3") (pinfunction "C_3") (pintype "passive"))
    )
    (net (code "24") (name "Net-(Q5-T_C)") (class "Default")
      (node (ref "D7") (pin "C") (pinfunction "C_C") (pintype "passive"))
      (node (ref "Q5") (pin "4") (pinfunction "T_C_4") (pintype "bidirectional"))
      (node (ref "Q6") (pin "1") (pinfunction "G_1") (pintype "passive"))
      (node (ref "R6") (pin "P$1") (pinfunction "1_P$1") (pintype "passive"))
    )
    (net (code "25") (name "Net-(Q6-D)") (class "Default")
      (node (ref "D6") (pin "C") (pinfunction "C_C") (pintype "passive"))
      (node (ref "D8") (pin "A") (pinfunction "A_A") (pintype "passive"))
      (node (ref "J3") (pin "1") (pinfunction "1_1") (pintype "bidirectional"))
      (node (ref "Q6") (pin "3") (pinfunction "D_3") (pintype "passive"))
    )
    (net (code "26") (name "Net-(Q7-C)") (class "Default")
      (node (ref "J8") (pin "2") (pinfunction "2_2") (pintype "bidirectional"))
      (node (ref "Q7") (pin "3") (pinfunction "C_3") (pintype "passive"))
      (node (ref "Q8") (pin "1") (pinfunction "B_1") (pintype "passive"))
      (node (ref "R5") (pin "P$1") (pinfunction "1_P$1") (pintype "passive"))
    )
    (net (code "27") (name "Net-(Q9-LED_A)") (class "Default")
      (node (ref "Q9") (pin "1") (pinfunction "LED_A_1") (pintype "bidirectional"))
      (node (ref "R12") (pin "P$1") (pinfunction "1_P$1") (pintype "passive"))
    )
    (net (code "28") (name "Net-(Q10-D)") (class "Default")
      (node (ref "D11") (pin "A") (pinfunction "A_A") (pintype "passive"))
      (node (ref "D9") (pin "C") (pinfunction "C_C") (pintype "passive"))
      (node (ref "J9") (pin "1") (pinfunction "1_1") (pintype "bidirectional"))
      (node (ref "Q10") (pin "3") (pinfunction "D_3") (pintype "passive"))
    )
    (net (code "29") (name "Net-(Q10-G)") (class "Default")
      (node (ref "D10") (pin "C") (pinfunction "C_C") (pintype "passive"))
      (node (ref "Q10") (pin "1") (pinfunction "G_1") (pintype "passive"))
      (node (ref "Q9") (pin "4") (pinfunction "T_C_4") (pintype "bidirectional"))
      (node (ref "R10") (pin "P$1") (pinfunction "1_P$1") (pintype "passive"))
    )
    (net (code "30") (name "Net-(Q11-C)") (class "Default")
      (node (ref "J10") (pin "2") (pinfunction "2_2") (pintype "bidirectional"))
      (node (ref "Q11") (pin "3") (pinfunction "C_3") (pintype "passive"))
      (node (ref "Q12") (pin "1") (pinfunction "B_1") (pintype "passive"))
      (node (ref "R9") (pin "P$1") (pinfunction "1_P$1") (pintype "passive"))
    )
    (net (code "31") (name "Net-(Q12-C)") (class "Default")
      (node (ref "J10") (pin "1") (pinfunction "1_1") (pintype "bidirectional"))
      (node (ref "Q12") (pin "3") (pinfunction "C_3") (pintype "passive"))
      (node (ref "Q9") (pin "2") (pinfunction "LED_C_2") (pintype "bidirectional"))
    )
    (net (code "32") (name "Net-(Q13-LED_A)") (class "Default")
      (node (ref "Q13") (pin "1") (pinfunction "LED_A_1") (pintype "bidirectional"))
      (node (ref "R16") (pin "P$1") (pinfunction "1_P$1") (pintype "passive"))
    )
    (net (code "33") (name "Net-(Q13-LED_C)") (class "Default")
      (node (ref "J12") (pin "1") (pinfunction "1_1") (pintype "bidirectional"))
      (node (ref "Q13") (pin "2") (pinfunction "LED_C_2") (pintype "bidirectional"))
      (node (ref "Q16") (pin "3") (pinfunction "C_3") (pintype "passive"))
    )
    (net (code "34") (name "Net-(Q13-T_C)") (class "Default")
      (node (ref "D13") (pin "C") (pinfunction "C_C") (pintype "passive"))
      (node (ref "Q13") (pin "4") (pinfunction "T_C_4") (pintype "bidirectional"))
      (node (ref "Q14") (pin "1") (pinfunction "G_1") (pintype "passive"))
      (node (ref "R14") (pin "P$1") (pinfunction "1_P$1") (pintype "passive"))
    )
    (net (code "35") (name "Net-(Q14-D)") (class "Default")
      (node (ref "D12") (pin "C") (pinfunction "C_C") (pintype "passive"))
      (node (ref "D14") (pin "A") (pinfunction "A_A") (pintype "passive"))
      (node (ref "J11") (pin "1") (pinfunction "1_1") (pintype "bidirectional"))
      (node (ref "Q14") (pin "3") (pinfunction "D_3") (pintype "passive"))
    )
    (net (code "36") (name "Net-(Q15-C)") (class "Default")
      (node (ref "J12") (pin "2") (pinfunction "2_2") (pintype "bidirectional"))
      (node (ref "Q15") (pin "3") (pinfunction "C_3") (pintype "passive"))
      (node (ref "Q16") (pin "1") (pinfunction "B_1") (pintype "passive"))
      (node (ref "R13") (pin "P$1") (pinfunction "1_P$1") (pintype "passive"))
    )
    (net (code "37") (name "VIN1") (class "Default")
      (node (ref "D1") (pin "C") (pinfunction "C_C") (pintype "passive"))
      (node (ref "R12") (pin "P$2") (pinfunction "2_P$2") (pintype "passive"))
      (node (ref "R13") (pin "P$2") (pinfunction "2_P$2") (pintype "passive"))
      (node (ref "R16") (pin "P$2") (pinfunction "2_P$2") (pintype "passive"))
      (node (ref "R2") (pin "P$2") (pinfunction "2_P$2") (pintype "passive"))
      (node (ref "R3") (pin "P$2") (pinfunction "2_P$2") (pintype "passive"))
      (node (ref "R5") (pin "P$2") (pinfunction "2_P$2") (pintype "passive"))
      (node (ref "R8") (pin "P$2") (pinfunction "2_P$2") (pintype "passive"))
      (node (ref "R9") (pin "P$2") (pinfunction "2_P$2") (pintype "passive"))
      (node (ref "TP1") (pin "TP") (pinfunction "TP_TP") (pintype "bidirectional"))
    )
    (net (code "38") (name "VIN1_DB9") (class "Default")
      (node (ref "J13") (pin "1") (pinfunction "1_1") (pintype "bidirectional"))
      (node (ref "J4") (pin "9") (pinfunction "9_9") (pintype "passive"))
    )
    (net (code "39") (name "VIN1_EXT") (class "Default")
      (node (ref "J1") (pin "1") (pinfunction "1_1") (pintype "bidirectional"))
      (node (ref "J6") (pin "1") (pinfunction "1_1") (pintype "bidirectional"))
    )
    (net (code "40") (name "VIN2") (class "Default")
      (node (ref "D11") (pin "C") (pinfunction "C_C") (pintype "passive"))
      (node (ref "D14") (pin "C") (pinfunction "C_C") (pintype "passive"))
      (node (ref "D2") (pin "C") (pinfunction "C_C") (pintype "passive"))
      (node (ref "D4") (pin "C") (pinfunction "C_C") (pintype "passive"))
      (node (ref "D8") (pin "C") (pinfunction "C_C") (pintype "passive"))
      (node (ref "J11") (pin "2") (pinfunction "2_2") (pintype "bidirectional"))
      (node (ref "J2") (pin "2") (pinfunction "2_2") (pintype "bidirectional"))
      (node (ref "J3") (pin "2") (pinfunction "2_2") (pintype "bidirectional"))
      (node (ref "J9") (pin "2") (pinfunction "2_2") (pintype "bidirectional"))
      (node (ref "R10") (pin "P$2") (pinfunction "2_P$2") (pintype "passive"))
      (node (ref "R14") (pin "P$2") (pinfunction "2_P$2") (pintype "passive"))
      (node (ref "R4") (pin "P$2") (pinfunction "2_P$2") (pintype "passive"))
      (node (ref "R6") (pin "P$2") (pinfunction "2_P$2") (pintype "passive"))
      (node (ref "TP2") (pin "TP") (pinfunction "TP_TP") (pintype "bidirectional"))
      (node (ref "U1") (pin "A") (pinfunction "A_A") (pintype "bidirectional"))
      (node (ref "U2") (pin "A") (pinfunction "A_A") (pintype "bidirectional"))
      (node (ref "U3") (pin "A") (pinfunction "A_A") (pintype "bidirectional"))
      (node (ref "U4") (pin "A") (pinfunction "A_A") (pintype "bidirectional"))
    )
    (net (code "41") (name "unconnected-(J4-Pad5)") (class "Default")
      (node (ref "J4") (pin "5") (pinfunction "5_5") (pintype "passive"))
    )
    (net (code "42") (name "unconnected-(J4-Pad7)") (class "Default")
      (node (ref "J4") (pin "7") (pinfunction "7_7") (pintype "passive"))
    )
    (net (code "43") (name "unconnected-(J4-Pad8)") (class "Default")
      (node (ref "J4") (pin "8") (pinfunction "8_8") (pintype "passive"))
    )
  )
)
